# MCU.net
KiCad netlist of a schematic drawn in Altium Designer
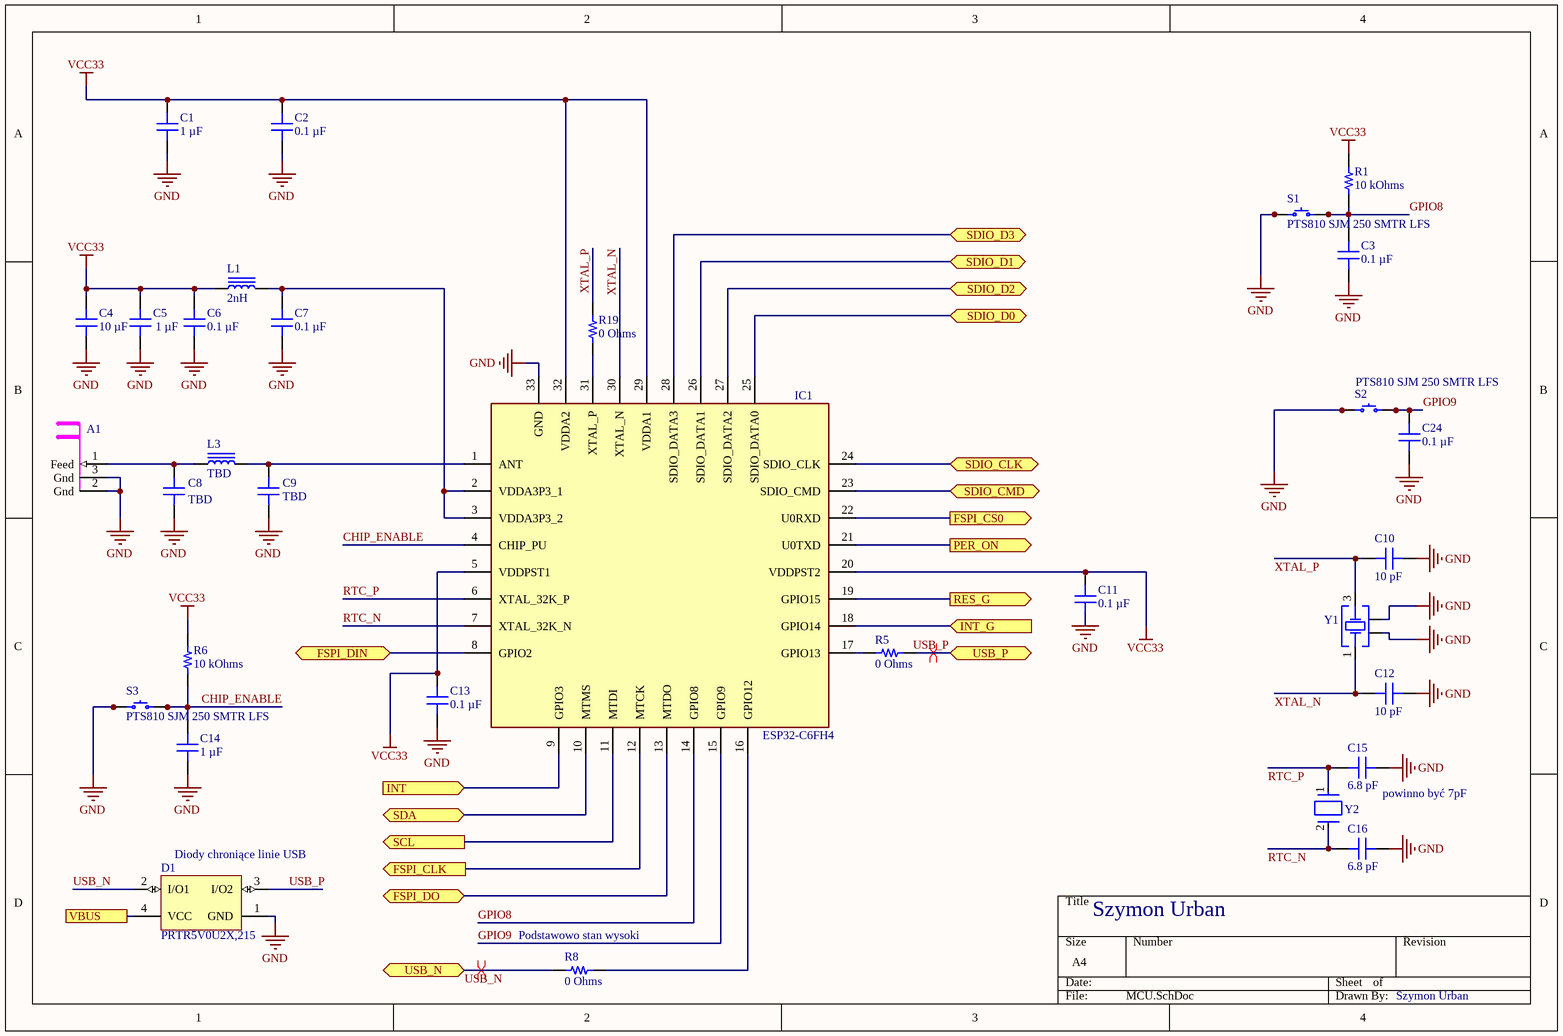
[diagram p0: MCU.SchDoc]

(export (version "E")
  (design (tool "Eeschema 10.0.6"))
  (components
    (comp (ref "A1")
      (value "Inverted F Antenna 2.4GHz")
      (footprint "IFA_2.4GHz")
      (libsource (lib "lib") (part "IFA_2.4GHz"))
    )
    (comp (ref "C1")
      (value "1 µF")
      (footprint "CAP 0603_1608")
      (description "CAP CER 1UF 10V X7R 0603")
      (fields (field (name "PART NUMBER") "CC0603KRX7R6BB105") (field (name "MANUFACTURER") "Yageo"))
      (libsource (lib "Celestial Altium Library - altium_library") (part "Capacitor"))
    )
    (comp (ref "C2")
      (value "0.1 µF")
      (footprint "CAP 0603_1608")
      (description "CAP CER 0.1UF 16V X7R 0603")
      (fields (field (name "PART NUMBER") "CS0603KRX7R7BB104") (field (name "MANUFACTURER") "Yageo"))
      (libsource (lib "Celestial Altium Library - altium_library") (part "Capacitor"))
    )
    (comp (ref "C3")
      (value "0.1 µF")
      (footprint "CAP 0603_1608")
      (description "CAP CER 0.1UF 16V X7R 0603")
      (fields (field (name "PART NUMBER") "CS0603KRX7R7BB104") (field (name "MANUFACTURER") "Yageo"))
      (libsource (lib "Celestial Altium Library - altium_library") (part "Capacitor"))
    )
    (comp (ref "C4")
      (value "10 µF")
      (footprint "CAP 0603_1608")
      (description "CAP CER 10UF 10V X7T 0603")
      (fields
        (field (name "PART NUMBER") "GRM188D71A106KA73D")
        (field (name "MANUFACTURER") "Murata Electronics")
      )
      (libsource (lib "Celestial Altium Library - altium_library") (part "Capacitor"))
    )
    (comp (ref "C5")
      (value "1 µF")
      (footprint "CAP 0603_1608")
      (description "CAP CER 1UF 10V X7R 0603")
      (fields
        (field (name "PART NUMBER") "CC0603KRX7R6BB105")
        (field (name "CAPACITANCE") "1 µF")
        (field (name "MANUFACTURER") "Yageo")
      )
      (libsource (lib "Celestial Altium Library - altium_library") (part "Capacitor"))
    )
    (comp (ref "C6")
      (value "0.1 µF")
      (footprint "CAP 0603_1608")
      (description "CAP CER 0.1UF 16V X7R 0603")
      (fields (field (name "PART NUMBER") "CS0603KRX7R7BB104") (field (name "MANUFACTURER") "Yageo"))
      (libsource (lib "Celestial Altium Library - altium_library") (part "Capacitor"))
    )
    (comp (ref "C7")
      (value "0.1 µF")
      (footprint "CAP 0603_1608")
      (description "CAP CER 0.1UF 16V X7R 0603")
      (fields (field (name "PART NUMBER") "CS0603KRX7R7BB104") (field (name "MANUFACTURER") "Yageo"))
      (libsource (lib "Celestial Altium Library - altium_library") (part "Capacitor"))
    )
    (comp (ref "C8")
      (value "TBD")
      (footprint "CAP 0402_1005")
      (description "CAP CER 6.8PF 25V C0G/NP0 0402")
      (fields (field (name "PART NUMBER") "04023A6R8CAT2A") (field (name "MANUFACTURER") "AVX Corporation"))
      (libsource (lib "Celestial Altium Library - altium_library") (part "Capacitor"))
    )
    (comp (ref "C9")
      (value "TBD")
      (footprint "CAP 0402_1005")
      (description "CAP CER 6.8PF 25V C0G/NP0 0402")
      (fields (field (name "PART NUMBER") "04023A6R8CAT2A") (field (name "MANUFACTURER") "AVX Corporation"))
      (libsource (lib "Celestial Altium Library - altium_library") (part "Capacitor"))
    )
    (comp (ref "C10")
      (value "10 pF")
      (footprint "CAP 0603_1608")
      (description "CAP CER 10PF 50V C0G/NP0 0603")
      (fields
        (field (name "PART NUMBER") "VJ0603A100FXACW1BC")
        (field (name "MANUFACTURER") "Vishay Vitramon")
      )
      (libsource (lib "Celestial Altium Library - altium_library") (part "Capacitor"))
    )
    (comp (ref "C11")
      (value "0.1 µF")
      (footprint "CAP 0603_1608")
      (description "CAP CER 0.1UF 16V X7R 0603")
      (fields (field (name "PART NUMBER") "CS0603KRX7R7BB104") (field (name "MANUFACTURER") "Yageo"))
      (libsource (lib "Celestial Altium Library - altium_library") (part "Capacitor"))
    )
    (comp (ref "C12")
      (value "10 pF")
      (footprint "CAP 0603_1608")
      (description "CAP CER 10PF 50V C0G/NP0 0603")
      (fields
        (field (name "PART NUMBER") "VJ0603A100FXACW1BC")
        (field (name "MANUFACTURER") "Vishay Vitramon")
      )
      (libsource (lib "Celestial Altium Library - altium_library") (part "Capacitor"))
    )
    (comp (ref "C13")
      (value "0.1 µF")
      (footprint "CAP 0603_1608")
      (description "CAP CER 0.1UF 16V X7R 0603")
      (fields (field (name "PART NUMBER") "CS0603KRX7R7BB104") (field (name "MANUFACTURER") "Yageo"))
      (libsource (lib "Celestial Altium Library - altium_library") (part "Capacitor"))
    )
    (comp (ref "C14")
      (value "1 µF")
      (footprint "CAP 0603_1608")
      (description "CAP CER 1UF 10V X7R 0603")
      (fields (field (name "PART NUMBER") "CC0603KRX7R6BB105") (field (name "MANUFACTURER") "Yageo"))
      (libsource (lib "Celestial Altium Library - altium_library") (part "Capacitor"))
    )
    (comp (ref "C15")
      (value "6.8 pF")
      (footprint "CAP 0603_1608")
      (description "CAP CER 6.8PF 250V C0G/NP0 0603")
      (fields
        (field (name "PART NUMBER") "GQM1875C2E6R8WB12D")
        (field (name "MANUFACTURER") "Murata Electronics")
      )
      (libsource (lib "Celestial Altium Library - altium_library") (part "Capacitor"))
    )
    (comp (ref "C16")
      (value "6.8 pF")
      (footprint "CAP 0603_1608")
      (description "CAP CER 6.8PF 250V C0G/NP0 0603")
      (fields
        (field (name "PART NUMBER") "GQM1875C2E6R8WB12D")
        (field (name "MANUFACTURER") "Murata Electronics")
      )
      (libsource (lib "Celestial Altium Library - altium_library") (part "Capacitor"))
    )
    (comp (ref "C24")
      (value "0.1 µF")
      (footprint "CAP 0603_1608")
      (description "CAP CER 0.1UF 16V X7R 0603")
      (fields (field (name "PART NUMBER") "CS0603KRX7R7BB104") (field (name "MANUFACTURER") "Yageo"))
      (libsource (lib "Celestial Altium Library - altium_library") (part "Capacitor"))
    )
    (comp (ref "D1")
      (value "PRTR5V0U2X,215")
      (footprint "NXP-SOT143B-4_V")
      (fields (field (name "MANUFACTURER") "NXP Semiconductors"))
      (libsource (lib "Altium Content Vault") (part "NXP-PRTR5V0U2X,215-4"))
    )
    (comp (ref "IC1")
      (value "ESP32-C6FH4")
      (footprint "lib:QFN50P500X500X90-33N")
      (description "Integrated Circuit")
      (fields (field (name "MOUSER PART NUMBER") "356-ESP32-C6FH4"))
      (libsource (lib "lib") (part "ESP32-C6FH4"))
    )
    (comp (ref "L1")
      (value "2nH")
      (footprint "IND 0603_1608 RF WW")
      (description "FIXED IND 2NH 700MA 80 MOHM SMD")
      (fields (field (name "PART NUMBER") "744761020A") (field (name "MANUFACTURER") "Würth Elektronik"))
      (libsource (lib "Celestial Altium Library - altium_library") (part "Inductor"))
    )
    (comp (ref "L3")
      (value "TBD")
      (footprint "IND 0402_1005 RF WW")
      (description "FIXED IND 390NH 100MA 4.35OHM SM")
      (fields
        (field (name "PART NUMBER") "LQW18ASR39J00D")
        (field (name "MANUFACTURER") "Murata Electronics")
      )
      (libsource (lib "Celestial Altium Library - altium_library") (part "Inductor"))
    )
    (comp (ref "R1")
      (value "10 kOhms")
      (footprint "RES 0603_1608")
      (description "RES SMD 10K OHM 1% 1/10W 0603")
      (fields (field (name "PART NUMBER") "RT0603FRE0710KL") (field (name "MANUFACTURER") "Yageo"))
      (libsource (lib "Celestial Altium Library - altium_library") (part "Resistor"))
    )
    (comp (ref "R5")
      (value "0 Ohms")
      (footprint "RES 0603_1608")
      (description "0603 26 AMP JUMPER")
      (fields (field (name "PART NUMBER") "JR0603X26E") (field (name "MANUFACTURER") "Ohmite"))
      (libsource (lib "Celestial Altium Library - altium_library") (part "Resistor"))
    )
    (comp (ref "R6")
      (value "10 kOhms")
      (footprint "RES 0603_1608")
      (description "RES SMD 10K OHM 1% 1/10W 0603")
      (fields (field (name "PART NUMBER") "RT0603FRE0710KL") (field (name "MANUFACTURER") "Yageo"))
      (libsource (lib "Celestial Altium Library - altium_library") (part "Resistor"))
    )
    (comp (ref "R8")
      (value "0 Ohms")
      (footprint "RES 0603_1608")
      (description "0603 26 AMP JUMPER")
      (fields (field (name "PART NUMBER") "JR0603X26E") (field (name "MANUFACTURER") "Ohmite"))
      (libsource (lib "Celestial Altium Library - altium_library") (part "Resistor"))
    )
    (comp (ref "R19")
      (value "0 Ohms")
      (footprint "RES 0603_1608")
      (description "0603 26 AMP JUMPER")
      (fields (field (name "PART NUMBER") "JR0603X26E") (field (name "MANUFACTURER") "Ohmite"))
      (libsource (lib "Celestial Altium Library - altium_library") (part "Resistor"))
    )
    (comp (ref "S1")
      (value "PTS810 SJM 250 SMTR LFS")
      (footprint "C&K PTS810")
      (description "SWITCH TACTILE SPST-NO 0.05A 16V")
      (fields (field (name "MANUFACTURER") "C&K"))
      (libsource (lib "Celestial Altium Library - altium_library") (part "SPST-NO 4 PIN"))
    )
    (comp (ref "S2")
      (value "PTS810 SJM 250 SMTR LFS")
      (footprint "C&K PTS810")
      (description "SWITCH TACTILE SPST-NO 0.05A 16V")
      (fields (field (name "MANUFACTURER") "C&K"))
      (libsource (lib "Celestial Altium Library - altium_library") (part "SPST-NO 4 PIN"))
    )
    (comp (ref "S3")
      (value "PTS810 SJM 250 SMTR LFS")
      (footprint "C&K PTS810")
      (description "SWITCH TACTILE SPST-NO 0.05A 16V")
      (fields (field (name "MANUFACTURER") "C&K"))
      (libsource (lib "Celestial Altium Library - altium_library") (part "SPST-NO 4 PIN"))
    )
    (comp (ref "Y1")
      (value "830108208709")
      (footprint "WE-XTAL_CFPX-218")
      (description "830108208709 WE-XTAL Quartz Crystal")
      (libsource (lib "Altium Content Vault") (part "WE-XTAL_CFPX-218"))
    )
    (comp (ref "Y2")
      (value "ABS07-32.768KHZ-7-1-T")
      (footprint "FP-ABS07-MFG")
      (description "Crystal 32.768kHz ±10ppm (Tol) 7pF FUND 70kΩ 2-Pin CSMD T/R")
      (libsource (lib "Altium Content Vault") (part "c23a69dc6c9e2f18f2079038eb95dd1"))
    )
  )
  (nets
    (net (code "1") (name "/CHIP_ENABLE") (class "Default")
      (node (ref "C14") (pin "2") (pinfunction "2_2") (pintype "passive"))
      (node (ref "IC1") (pin "4") (pinfunction "CHIP_PU_4") (pintype "passive"))
      (node (ref "R6") (pin "1") (pinfunction "1_1") (pintype "passive"))
      (node (ref "S3") (pin "3") (pinfunction "3_3") (pintype "passive"))
      (node (ref "S3") (pin "4") (pinfunction "4_4") (pintype "passive"))
    )
    (net (code "2") (name "/FSPI_CLK") (class "Default")
      (node (ref "IC1") (pin "12") (pinfunction "MTCK_12") (pintype "passive"))
    )
    (net (code "3") (name "/FSPI_CS0") (class "Default")
      (node (ref "IC1") (pin "22") (pinfunction "U0RXD_22") (pintype "passive"))
    )
    (net (code "4") (name "/FSPI_DIN") (class "Default")
      (node (ref "IC1") (pin "8") (pinfunction "GPIO2_8") (pintype "passive"))
    )
    (net (code "5") (name "/FSPI_DO") (class "Default")
      (node (ref "IC1") (pin "13") (pinfunction "MTDO_13") (pintype "passive"))
    )
    (net (code "6") (name "/GPIO8") (class "Default")
      (node (ref "C3") (pin "2") (pinfunction "2_2") (pintype "passive"))
      (node (ref "IC1") (pin "14") (pinfunction "GPIO8_14") (pintype "passive"))
      (node (ref "R1") (pin "1") (pinfunction "1_1") (pintype "passive"))
      (node (ref "S1") (pin "3") (pinfunction "3_3") (pintype "passive"))
      (node (ref "S1") (pin "4") (pinfunction "4_4") (pintype "passive"))
    )
    (net (code "7") (name "/GPIO9") (class "Default")
      (node (ref "C24") (pin "2") (pinfunction "2_2") (pintype "passive"))
      (node (ref "IC1") (pin "15") (pinfunction "GPIO9_15") (pintype "passive"))
      (node (ref "S2") (pin "3") (pinfunction "3_3") (pintype "passive"))
      (node (ref "S2") (pin "4") (pinfunction "4_4") (pintype "passive"))
    )
    (net (code "8") (name "/INT") (class "Default")
      (node (ref "IC1") (pin "9") (pinfunction "GPIO3_9") (pintype "passive"))
    )
    (net (code "9") (name "/INT_G") (class "Default")
      (node (ref "IC1") (pin "18") (pinfunction "GPIO14_18") (pintype "passive"))
    )
    (net (code "10") (name "/PER_ON") (class "Default")
      (node (ref "IC1") (pin "21") (pinfunction "U0TXD_21") (pintype "passive"))
    )
    (net (code "11") (name "/RES_G") (class "Default")
      (node (ref "IC1") (pin "19") (pinfunction "GPIO15_19") (pintype "passive"))
    )
    (net (code "12") (name "/RTC_N") (class "Default")
      (node (ref "C16") (pin "1") (pinfunction "1_1") (pintype "passive"))
      (node (ref "IC1") (pin "7") (pinfunction "XTAL_32K_N_7") (pintype "passive"))
      (node (ref "Y2") (pin "2") (pinfunction "2_2") (pintype "passive"))
    )
    (net (code "13") (name "/RTC_P") (class "Default")
      (node (ref "C15") (pin "1") (pinfunction "1_1") (pintype "passive"))
      (node (ref "IC1") (pin "6") (pinfunction "XTAL_32K_P_6") (pintype "passive"))
      (node (ref "Y2") (pin "1") (pinfunction "1_1") (pintype "passive"))
    )
    (net (code "14") (name "/SCL") (class "Default")
      (node (ref "IC1") (pin "11") (pinfunction "MTDI_11") (pintype "passive"))
    )
    (net (code "15") (name "/SDA") (class "Default")
      (node (ref "IC1") (pin "10") (pinfunction "MTMS_10") (pintype "passive"))
    )
    (net (code "16") (name "/SDIO_CLK") (class "Default")
      (node (ref "IC1") (pin "24") (pinfunction "SDIO_CLK_24") (pintype "passive"))
    )
    (net (code "17") (name "/SDIO_CMD") (class "Default")
      (node (ref "IC1") (pin "23") (pinfunction "SDIO_CMD_23") (pintype "passive"))
    )
    (net (code "18") (name "/SDIO_D0") (class "Default")
      (node (ref "IC1") (pin "25") (pinfunction "SDIO_DATA0_25") (pintype "passive"))
    )
    (net (code "19") (name "/SDIO_D1") (class "Default")
      (node (ref "IC1") (pin "26") (pinfunction "SDIO_DATA1_26") (pintype "passive"))
    )
    (net (code "20") (name "/SDIO_D2") (class "Default")
      (node (ref "IC1") (pin "27") (pinfunction "SDIO_DATA2_27") (pintype "passive"))
    )
    (net (code "21") (name "/SDIO_D3") (class "Default")
      (node (ref "IC1") (pin "28") (pinfunction "SDIO_DATA3_28") (pintype "passive"))
    )
    (net (code "22") (name "/USB_N") (class "Default")
      (node (ref "D1") (pin "2") (pinfunction "I/O1_2") (pintype "bidirectional"))
      (node (ref "R8") (pin "2") (pinfunction "2_2") (pintype "passive"))
    )
    (net (code "23") (name "/USB_P") (class "Default")
      (node (ref "D1") (pin "3") (pinfunction "I/O2_3") (pintype "bidirectional"))
      (node (ref "R5") (pin "1") (pinfunction "1_1") (pintype "passive"))
    )
    (net (code "24") (name "/VBUS") (class "Default")
      (node (ref "D1") (pin "4") (pinfunction "VCC_4") (pintype "power_in"))
    )
    (net (code "25") (name "/XTAL_N") (class "Default")
      (node (ref "C12") (pin "1") (pinfunction "1_1") (pintype "passive"))
      (node (ref "IC1") (pin "30") (pinfunction "XTAL_N_30") (pintype "passive"))
      (node (ref "Y1") (pin "1") (pinfunction "Crystal_1") (pintype "passive"))
    )
    (net (code "26") (name "/XTAL_P") (class "Default")
      (node (ref "C10") (pin "1") (pinfunction "1_1") (pintype "passive"))
      (node (ref "R19") (pin "1") (pinfunction "1_1") (pintype "passive"))
      (node (ref "Y1") (pin "3") (pinfunction "Crystal_3") (pintype "passive"))
    )
    (net (code "27") (name "GND") (class "Default")
      (node (ref "A1") (pin "2") (pinfunction "Gnd_2") (pintype "power_in"))
      (node (ref "A1") (pin "3") (pinfunction "Gnd_3") (pintype "power_in"))
      (node (ref "C1") (pin "1") (pinfunction "1_1") (pintype "passive"))
      (node (ref "C10") (pin "2") (pinfunction "2_2") (pintype "passive"))
      (node (ref "C11") (pin "1") (pinfunction "1_1") (pintype "passive"))
      (node (ref "C12") (pin "2") (pinfunction "2_2") (pintype "passive"))
      (node (ref "C13") (pin "1") (pinfunction "1_1") (pintype "passive"))
      (node (ref "C14") (pin "1") (pinfunction "1_1") (pintype "passive"))
      (node (ref "C15") (pin "2") (pinfunction "2_2") (pintype "passive"))
      (node (ref "C16") (pin "2") (pinfunction "2_2") (pintype "passive"))
      (node (ref "C2") (pin "1") (pinfunction "1_1") (pintype "passive"))
      (node (ref "C24") (pin "1") (pinfunction "1_1") (pintype "passive"))
      (node (ref "C3") (pin "1") (pinfunction "1_1") (pintype "passive"))
      (node (ref "C4") (pin "2") (pinfunction "2_2") (pintype "passive"))
      (node (ref "C5") (pin "1") (pinfunction "1_1") (pintype "passive"))
      (node (ref "C6") (pin "1") (pinfunction "1_1") (pintype "passive"))
      (node (ref "C7") (pin "1") (pinfunction "1_1") (pintype "passive"))
      (node (ref "C8") (pin "1") (pinfunction "1_1") (pintype "passive"))
      (node (ref "C9") (pin "1") (pinfunction "1_1") (pintype "passive"))
      (node (ref "D1") (pin "1") (pinfunction "GND_1") (pintype "power_in"))
      (node (ref "IC1") (pin "33") (pinfunction "GND_33") (pintype "passive"))
      (node (ref "S1") (pin "1") (pinfunction "1_1") (pintype "passive"))
      (node (ref "S1") (pin "2") (pinfunction "2_2") (pintype "passive"))
      (node (ref "S2") (pin "1") (pinfunction "1_1") (pintype "passive"))
      (node (ref "S2") (pin "2") (pinfunction "2_2") (pintype "passive"))
      (node (ref "S3") (pin "1") (pinfunction "1_1") (pintype "passive"))
      (node (ref "S3") (pin "2") (pinfunction "2_2") (pintype "passive"))
      (node (ref "Y1") (pin "2") (pinfunction "GND_2") (pintype "passive"))
      (node (ref "Y1") (pin "4") (pinfunction "GND_4") (pintype "passive"))
    )
    (net (code "28") (name "Net-(A1-Feed)") (class "Default")
      (node (ref "A1") (pin "1") (pinfunction "Feed_1") (pintype "input"))
      (node (ref "C8") (pin "2") (pinfunction "2_2") (pintype "passive"))
      (node (ref "L3") (pin "1") (pinfunction "1_1") (pintype "passive"))
    )
    (net (code "29") (name "Net-(IC1-ANT)") (class "Default")
      (node (ref "C9") (pin "2") (pinfunction "2_2") (pintype "passive"))
      (node (ref "IC1") (pin "1") (pinfunction "ANT_1") (pintype "passive"))
      (node (ref "L3") (pin "2") (pinfunction "2_2") (pintype "passive"))
    )
    (net (code "30") (name "Net-(IC1-GPIO12)") (class "Default")
      (node (ref "IC1") (pin "16") (pinfunction "GPIO12_16") (pintype "passive"))
      (node (ref "R8") (pin "1") (pinfunction "1_1") (pintype "passive"))
    )
    (net (code "31") (name "Net-(IC1-GPIO13)") (class "Default")
      (node (ref "IC1") (pin "17") (pinfunction "GPIO13_17") (pintype "passive"))
      (node (ref "R5") (pin "2") (pinfunction "2_2") (pintype "passive"))
    )
    (net (code "32") (name "Net-(IC1-VDDA3P3_1)") (class "Default")
      (node (ref "C7") (pin "2") (pinfunction "2_2") (pintype "passive"))
      (node (ref "IC1") (pin "2") (pinfunction "VDDA3P3_1_2") (pintype "passive"))
      (node (ref "IC1") (pin "3") (pinfunction "VDDA3P3_2_3") (pintype "passive"))
      (node (ref "L1") (pin "2") (pinfunction "2_2") (pintype "passive"))
    )
    (net (code "33") (name "Net-(IC1-XTAL_P)") (class "Default")
      (node (ref "IC1") (pin "31") (pinfunction "XTAL_P_31") (pintype "passive"))
      (node (ref "R19") (pin "2") (pinfunction "2_2") (pintype "passive"))
    )
    (net (code "34") (name "VCC33") (class "Default")
      (node (ref "C1") (pin "2") (pinfunction "2_2") (pintype "passive"))
      (node (ref "C11") (pin "2") (pinfunction "2_2") (pintype "passive"))
      (node (ref "C13") (pin "2") (pinfunction "2_2") (pintype "passive"))
      (node (ref "C2") (pin "2") (pinfunction "2_2") (pintype "passive"))
      (node (ref "C4") (pin "1") (pinfunction "1_1") (pintype "passive"))
      (node (ref "C5") (pin "2") (pinfunction "2_2") (pintype "passive"))
      (node (ref "C6") (pin "2") (pinfunction "2_2") (pintype "passive"))
      (node (ref "IC1") (pin "20") (pinfunction "VDDPST2_20") (pintype "passive"))
      (node (ref "IC1") (pin "29") (pinfunction "VDDA1_29") (pintype "passive"))
      (node (ref "IC1") (pin "32") (pinfunction "VDDA2_32") (pintype "passive"))
      (node (ref "IC1") (pin "5") (pinfunction "VDDPST1_5") (pintype "passive"))
      (node (ref "L1") (pin "1") (pinfunction "1_1") (pintype "passive"))
      (node (ref "R1") (pin "2") (pinfunction "2_2") (pintype "passive"))
      (node (ref "R6") (pin "2") (pinfunction "2_2") (pintype "passive"))
    )
  )
)
